# L298BOB.net
KiCad netlist of a schematic drawn in EAGLE
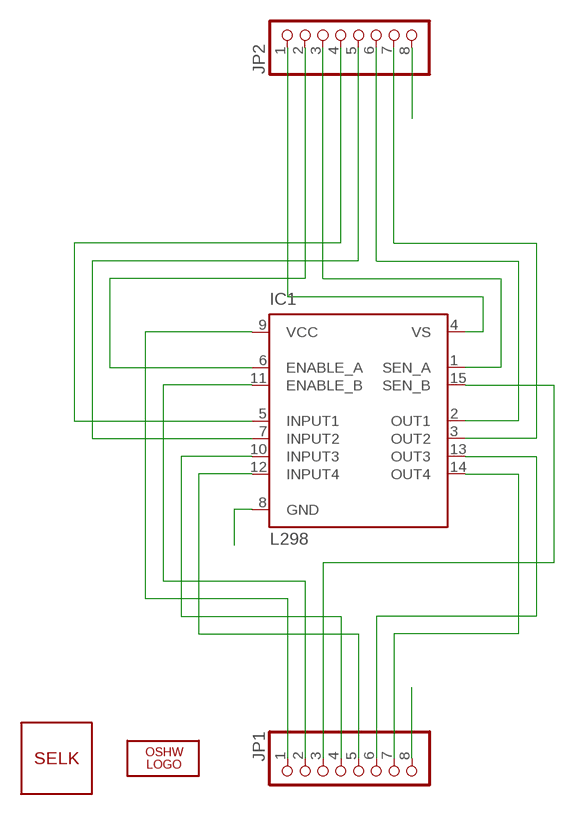
[diagram p0: schematic, sheet 1]

(export (version "E")
  (design (tool "Eeschema 10.0.6"))
  (components
    (comp (ref "IC1")
      (value "L298")
      (footprint "eagle-import:MULTIWATT-15")
      (fields (field (name "MPN") "L298N"))
      (libsource (lib "eagle-import") (part "L298"))
    )
    (comp (ref "JP1")
      (value "PINHD-1X8")
      (footprint "eagle-import:1X08")
      (libsource (lib "eagle-import") (part "PINHD-1X8"))
    )
    (comp (ref "JP2")
      (value "PINHD-1X8")
      (footprint "eagle-import:1X08")
      (libsource (lib "eagle-import") (part "PINHD-1X8"))
    )
    (comp (ref "LOGO1")
      (value "OSHW_LOGO_FILLX0200-NT")
      (footprint "eagle-import:OSHW_FILLX200_NOTEXT")
      (libsource (lib "eagle-import") (part "OSHW_LOGO_FILLX0200-NT"))
    )
    (comp (ref "U$1")
      (value "SELK02")
      (footprint "eagle-import:SELK02")
      (libsource (lib "eagle-import") (part "SELK02"))
    )
  )
  (nets
    (net (code "1") (name "/GND") (class "Default")
      (node (ref "IC1") (pin "8") (pinfunction "GND_8") (pintype "power_in"))
      (node (ref "JP1") (pin "8") (pinfunction "8_8") (pintype "passive"))
      (node (ref "JP2") (pin "8") (pinfunction "8_8") (pintype "passive"))
    )
    (net (code "2") (name "Net-(IC1-ENABLE_A)") (class "Default")
      (node (ref "IC1") (pin "6") (pinfunction "ENABLE_A_6") (pintype "input"))
      (node (ref "JP2") (pin "2") (pinfunction "2_2") (pintype "passive"))
    )
    (net (code "3") (name "Net-(IC1-ENABLE_B)") (class "Default")
      (node (ref "IC1") (pin "11") (pinfunction "ENABLE_B_11") (pintype "input"))
      (node (ref "JP1") (pin "2") (pinfunction "2_2") (pintype "passive"))
    )
    (net (code "4") (name "Net-(IC1-INPUT1)") (class "Default")
      (node (ref "IC1") (pin "5") (pinfunction "INPUT1_5") (pintype "input"))
      (node (ref "JP2") (pin "4") (pinfunction "4_4") (pintype "passive"))
    )
    (net (code "5") (name "Net-(IC1-INPUT2)") (class "Default")
      (node (ref "IC1") (pin "7") (pinfunction "INPUT2_7") (pintype "input"))
      (node (ref "JP2") (pin "5") (pinfunction "5_5") (pintype "passive"))
    )
    (net (code "6") (name "Net-(IC1-INPUT3)") (class "Default")
      (node (ref "IC1") (pin "10") (pinfunction "INPUT3_10") (pintype "input"))
      (node (ref "JP1") (pin "4") (pinfunction "4_4") (pintype "passive"))
    )
    (net (code "7") (name "Net-(IC1-INPUT4)") (class "Default")
      (node (ref "IC1") (pin "12") (pinfunction "INPUT4_12") (pintype "input"))
      (node (ref "JP1") (pin "5") (pinfunction "5_5") (pintype "passive"))
    )
    (net (code "8") (name "Net-(IC1-OUT1)") (class "Default")
      (node (ref "IC1") (pin "2") (pinfunction "OUT1_2") (pintype "output"))
      (node (ref "JP2") (pin "6") (pinfunction "6_6") (pintype "passive"))
    )
    (net (code "9") (name "Net-(IC1-OUT2)") (class "Default")
      (node (ref "IC1") (pin "3") (pinfunction "OUT2_3") (pintype "output"))
      (node (ref "JP2") (pin "7") (pinfunction "7_7") (pintype "passive"))
    )
    (net (code "10") (name "Net-(IC1-OUT3)") (class "Default")
      (node (ref "IC1") (pin "13") (pinfunction "OUT3_13") (pintype "output"))
      (node (ref "JP1") (pin "6") (pinfunction "6_6") (pintype "passive"))
    )
    (net (code "11") (name "Net-(IC1-OUT4)") (class "Default")
      (node (ref "IC1") (pin "14") (pinfunction "OUT4_14") (pintype "output"))
      (node (ref "JP1") (pin "7") (pinfunction "7_7") (pintype "passive"))
    )
    (net (code "12") (name "Net-(IC1-SEN_A)") (class "Default")
      (node (ref "IC1") (pin "1") (pinfunction "SEN_A_1") (pintype "input"))
      (node (ref "JP2") (pin "3") (pinfunction "3_3") (pintype "passive"))
    )
    (net (code "13") (name "Net-(IC1-SEN_B)") (class "Default")
      (node (ref "IC1") (pin "15") (pinfunction "SEN_B_15") (pintype "input"))
      (node (ref "JP1") (pin "3") (pinfunction "3_3") (pintype "passive"))
    )
    (net (code "14") (name "Net-(IC1-VCC)") (class "Default")
      (node (ref "IC1") (pin "9") (pinfunction "VCC_9") (pintype "power_in"))
      (node (ref "JP1") (pin "1") (pinfunction "1_1") (pintype "passive"))
    )
    (net (code "15") (name "Net-(IC1-VS)") (class "Default")
      (node (ref "IC1") (pin "4") (pinfunction "VS_4") (pintype "power_in"))
      (node (ref "JP2") (pin "1") (pinfunction "1_1") (pintype "passive"))
    )
  )
)
